# Sensor_Board.net
KiCad netlist of a schematic drawn in Altium Designer
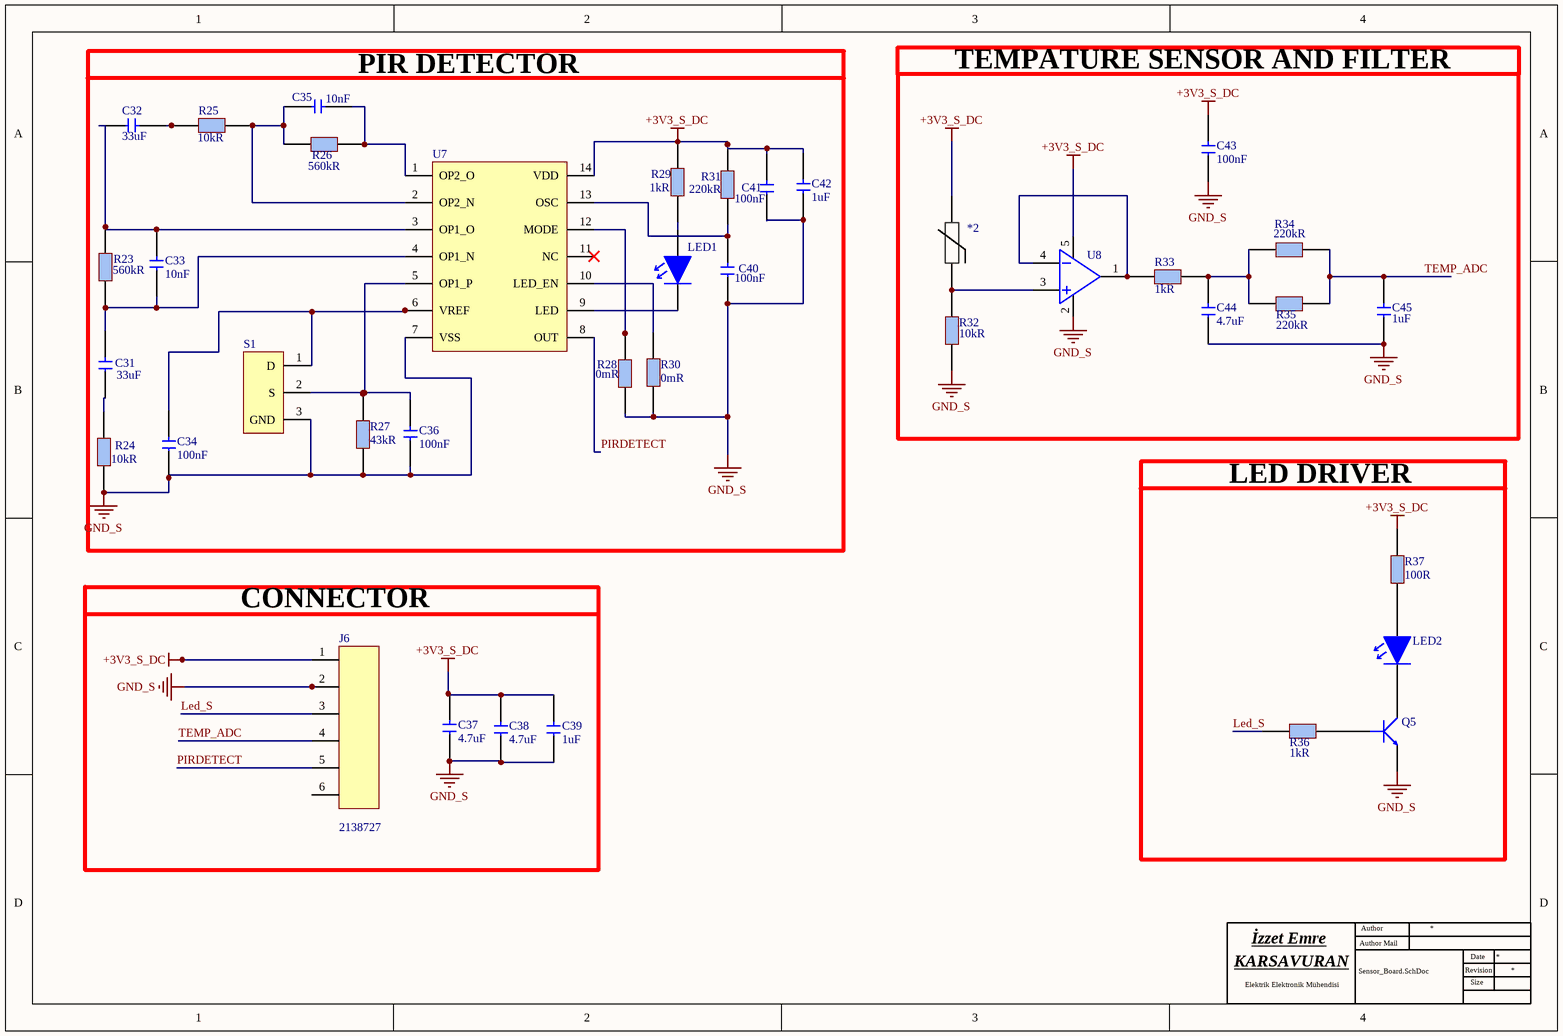
[diagram p0: Sensor_Board.SchDoc]

(export (version "E")
  (design (tool "Eeschema 10.0.6"))
  (components
    (comp (ref "*2")
      (value "TFPT1206L1002FM")
      (footprint "RES_1206")
      (description "Thermistor PTC 10K Ohm 1% 2-Pin 1206 Surface Mount Solder Pad T/R Automotive")
      (fields
        (field (name "MANUFACTURER") "Vishay Dale")
        (field (name "TOLERANCE") "1%")
        (field (name "DESIGNED BY") "İzzet Emre KARSAVURAN")
      )
      (libsource (lib "burglar_alarm_system_Library") (part "TFPT1206L1002FM"))
    )
    (comp (ref "C31")
      (value "C3216X5R1E336M160AC")
      (footprint "CAP_1206")
      (description "Cap Ceramic 33uF 25V X5R 20% SMD 1206 85C T/R")
      (fields
        (field (name "MANUFACTURER") "TDK")
        (field (name "TOLERANCE") "20%")
        (field (name "CAPACITANCE") "33uF")
        (field (name "DESIGNED BY") "İzzet Emre KARSAVURAN")
      )
      (libsource (lib "burglar_alarm_system_Library") (part "CAP CER 33uF"))
    )
    (comp (ref "C32")
      (value "C3216X5R1E336M160AC")
      (footprint "CAP_1206")
      (description "Cap Ceramic 33uF 25V X5R 20% SMD 1206 85C T/R")
      (fields
        (field (name "MANUFACTURER") "TDK")
        (field (name "TOLERANCE") "20%")
        (field (name "CAPACITANCE") "33uF")
        (field (name "DESIGNED BY") "İzzet Emre KARSAVURAN")
      )
      (libsource (lib "burglar_alarm_system_Library") (part "CAP CER 33uF"))
    )
    (comp (ref "C33")
      (value "0603B103K160CT")
      (footprint "CAP_0603")
      (fields
        (field (name "MANUFACTURER") "Walsin Technologies")
        (field (name "TOLERANCE") "10%")
        (field (name "CAPACITANCE") "10nF")
        (field (name "DESIGNED BY") "İzzet Emre KARSAVURAN")
      )
      (libsource (lib "burglar_alarm_system_Library") (part "CAP CER 10nF"))
    )
    (comp (ref "C34")
      (value "CL21B104KBCNNNC")
      (footprint "CAP_0805")
      (fields
        (field (name "MANUFACTURER") "Samsung")
        (field (name "TOLERANCE") "10%")
        (field (name "VOLTAGE") "50V")
        (field (name "CAPACITANCE") "100nF")
        (field (name "DESIGNED BY") "İzzet Emre KARSAVURAN")
      )
      (libsource (lib "burglar_alarm_system_Library") (part "CAP CER 100nF-0803"))
    )
    (comp (ref "C35")
      (value "0603B103K160CT")
      (footprint "CAP_0603")
      (fields
        (field (name "MANUFACTURER") "Walsin Technologies")
        (field (name "TOLERANCE") "10%")
        (field (name "CAPACITANCE") "10nF")
        (field (name "DESIGNED BY") "İzzet Emre KARSAVURAN")
      )
      (libsource (lib "burglar_alarm_system_Library") (part "CAP CER 10nF"))
    )
    (comp (ref "C36")
      (value "CL21B104KBCNNNC")
      (footprint "CAP_0805")
      (fields
        (field (name "MANUFACTURER") "Samsung")
        (field (name "TOLERANCE") "10%")
        (field (name "VOLTAGE") "50V")
        (field (name "CAPACITANCE") "100nF")
        (field (name "DESIGNED BY") "İzzet Emre KARSAVURAN")
      )
      (libsource (lib "burglar_alarm_system_Library") (part "CAP CER 100nF-0803"))
    )
    (comp (ref "C37")
      (value "CL21A475KAQNNNE")
      (footprint "CAP_0805")
      (fields
        (field (name "MANUFACTURER") "Samsung")
        (field (name "TOLERANCE") "10%")
        (field (name "CAPACITANCE") "4.7uF")
        (field (name "DESIGNED BY") "İzzet Emre KARSAVURAN")
      )
      (libsource (lib "burglar_alarm_system_Library") (part "CAP CER 4.7uF"))
    )
    (comp (ref "C38")
      (value "CL21A475KAQNNNE")
      (footprint "CAP_0805")
      (fields
        (field (name "MANUFACTURER") "Samsung")
        (field (name "TOLERANCE") "10%")
        (field (name "CAPACITANCE") "4.7uF")
        (field (name "DESIGNED BY") "İzzet Emre KARSAVURAN")
      )
      (libsource (lib "burglar_alarm_system_Library") (part "CAP CER 4.7uF"))
    )
    (comp (ref "C39")
      (value "CL21B105KBFNNNE")
      (footprint "CAP_0805")
      (fields
        (field (name "MANUFACTURER") "Samsung")
        (field (name "TOLERANCE") "10%")
        (field (name "VOLTAGE") "50V")
        (field (name "CAPACITANCE") "1uF")
        (field (name "DESIGNED BY") "İzzet Emre KARSAVURAN")
      )
      (libsource (lib "burglar_alarm_system_Library") (part "CAP CER 1uF"))
    )
    (comp (ref "C40")
      (value "CL21B104KBCNNNC")
      (footprint "CAP_0805")
      (fields
        (field (name "MANUFACTURER") "Samsung")
        (field (name "TOLERANCE") "10%")
        (field (name "VOLTAGE") "50V")
        (field (name "CAPACITANCE") "100nF")
        (field (name "DESIGNED BY") "İzzet Emre KARSAVURAN")
      )
      (libsource (lib "burglar_alarm_system_Library") (part "CAP CER 100nF-0803"))
    )
    (comp (ref "C41")
      (value "CL21B104KBCNNNC")
      (footprint "CAP_0805")
      (fields
        (field (name "MANUFACTURER") "Samsung")
        (field (name "TOLERANCE") "10%")
        (field (name "VOLTAGE") "50V")
        (field (name "CAPACITANCE") "100nF")
        (field (name "DESIGNED BY") "İzzet Emre KARSAVURAN")
      )
      (libsource (lib "burglar_alarm_system_Library") (part "CAP CER 100nF-0803"))
    )
    (comp (ref "C42")
      (value "CL21B105KBFNNNE")
      (footprint "CAP_0805")
      (fields
        (field (name "MANUFACTURER") "Samsung")
        (field (name "TOLERANCE") "10%")
        (field (name "VOLTAGE") "50V")
        (field (name "CAPACITANCE") "1uF")
        (field (name "DESIGNED BY") "İzzet Emre KARSAVURAN")
      )
      (libsource (lib "burglar_alarm_system_Library") (part "CAP CER 1uF"))
    )
    (comp (ref "C43")
      (value "C0603C104K5RACTU")
      (footprint "CAP_0603")
      (description "Multilayer Ceramic Capacitors (MLCC) - SMD/SMT 50volts 0.1uF X7R 10%")
      (fields
        (field (name "MANUFACTURER") "KEMET")
        (field (name "TOLERANCE") "10%")
        (field (name "CAPACITANCE") "100nF")
        (field (name "DESIGNED BY") "İzzet Emre KARSAVURAN")
      )
      (libsource (lib "burglar_alarm_system_Library") (part "CAP CER 100nF 0603"))
    )
    (comp (ref "C44")
      (value "CL21A475KAQNNNE")
      (footprint "CAP_0805")
      (fields
        (field (name "MANUFACTURER") "Samsung")
        (field (name "TOLERANCE") "10%")
        (field (name "CAPACITANCE") "4.7uF")
        (field (name "DESIGNED BY") "İzzet Emre KARSAVURAN")
      )
      (libsource (lib "burglar_alarm_system_Library") (part "CAP CER 4.7uF"))
    )
    (comp (ref "C45")
      (value "CL21B105KBFNNNE")
      (footprint "CAP_0805")
      (fields
        (field (name "MANUFACTURER") "Samsung")
        (field (name "TOLERANCE") "10%")
        (field (name "VOLTAGE") "50V")
        (field (name "CAPACITANCE") "1uF")
        (field (name "DESIGNED BY") "İzzet Emre KARSAVURAN")
      )
      (libsource (lib "burglar_alarm_system_Library") (part "CAP CER 1uF"))
    )
    (comp (ref "J6")
      (value "64800611622")
      (footprint "64800611622")
      (fields
        (field (name "MANUFACTURER") "Wurth Electronics")
        (field (name "SUPPLIER PART NUMBER 1") "2138727")
        (field (name "DESIGNED BY") "İzzet Emre KARSAVURAN")
      )
      (libsource (lib "burglar_alarm_system_Library") (part "64800611622_conn_6pin"))
    )
    (comp (ref "LED1")
      (value "LTST-C171GKT")
      (footprint "LED_GREEN_0805")
      (description "Green 0805 130 º Min 5 mcd Typical 12 mcd Water Clear Lens SMT LED")
      (fields
        (field (name "MANUFACTURER") "Vishay Lite-On")
        (field (name "DESIGNED BY") "İzzet Emre KARSAVURAN")
      )
      (libsource (lib "burglar_alarm_system_Library") (part "LED GREEN 0805"))
    )
    (comp (ref "LED2")
      (value "LH R974-LP-1")
      (footprint "LED_RED_0805")
      (description "LED Uni-Color Red 660nm T/R")
      (fields (field (name "MANUFACTURER") "Osram Opto") (field (name "DESIGNED BY") "İzzet Emre KARSAVURAN"))
      (libsource (lib "burglar_alarm_system_Library") (part "LED RED 0805"))
    )
    (comp (ref "Q5")
      (value "MMBT3904-7-F")
      (footprint "SOT23-F")
      (description "TRANS NPN 40V 0.2A SMD SOT23-3")
      (fields
        (field (name "MANUFACTURER") "Diodes Zetex")
        (field (name "DESIGNED BY") "İzzet Emre KARSAVURAN")
      )
      (libsource (lib "burglar_alarm_system_Library") (part "MMBT3904-7-F"))
    )
    (comp (ref "R23")
      (value "RC0603JR-07560KL")
      (footprint "RES_0603")
      (description "RES SMD 560K OHM 5% 1/10W 0603")
      (fields
        (field (name "MANUFACTURER") "Yageo")
        (field (name "TOLERANCE") "5%")
        (field (name "RESISTANCE") "560kR")
        (field (name "DESIGNED BY") "İzzet Emre KARSAVURAN")
      )
      (libsource (lib "") (part "RES 560k OHM_1"))
    )
    (comp (ref "R24")
      (value "RC0603FR-0710KL")
      (footprint "RES_0603")
      (description "Res General Purpose Thick Film 0603 10K Ohm 1% 1/10W ±100ppm/°C Molded SMD Paper T/R")
      (fields
        (field (name "MANUFACTURER") "Yageo")
        (field (name "TOLERANCE") "1%")
        (field (name "RESISTANCE") "10kR")
        (field (name "DESIGNED BY") "İzzet Emre Karsavuran")
      )
      (libsource (lib "") (part "RES 10K OHM 0603_1"))
    )
    (comp (ref "R25")
      (value "RC0603FR-0710KL")
      (footprint "RES_0603")
      (description "Res General Purpose Thick Film 0603 10K Ohm 1% 1/10W ±100ppm/°C Molded SMD Paper T/R")
      (fields
        (field (name "MANUFACTURER") "Yageo")
        (field (name "TOLERANCE") "1%")
        (field (name "RESISTANCE") "10kR")
        (field (name "DESIGNED BY") "İzzet Emre Karsavuran")
      )
      (libsource (lib "burglar_alarm_system_Library") (part "RES 10K OHM 0603"))
    )
    (comp (ref "R26")
      (value "RC0603JR-07560KL")
      (footprint "RES_0603")
      (description "RES SMD 560K OHM 5% 1/10W 0603")
      (fields
        (field (name "MANUFACTURER") "Yageo")
        (field (name "TOLERANCE") "5%")
        (field (name "RESISTANCE") "560kR")
        (field (name "DESIGNED BY") "İzzet Emre KARSAVURAN")
      )
      (libsource (lib "burglar_alarm_system_Library") (part "RES 560k OHM"))
    )
    (comp (ref "R27")
      (value "RC0603JR-0743KL")
      (footprint "RES_0603")
      (fields
        (field (name "MANUFACTURER") "Yageo")
        (field (name "TOLERANCE") "5%")
        (field (name "RESISTANCE") "43kR")
        (field (name "DESIGNED BY") "İzzet Emre KARSAVURAN")
      )
      (libsource (lib "burglar_alarm_system_Library") (part "RES 43K OHM"))
    )
    (comp (ref "R28")
      (value "RC0603JR-070RL")
      (footprint "RES_0603")
      (description "RES SMD 0 OHM JUMPER 1/10W 0603")
      (fields
        (field (name "MANUFACTURER") "Yageo")
        (field (name "TOLERANCE") "1%")
        (field (name "RESISTANCE") "0mR")
        (field (name "DESIGNED BY") "İzzet Emre Karsavuran")
      )
      (libsource (lib "burglar_alarm_system_Library") (part "RES 0 OHM"))
    )
    (comp (ref "R29")
      (value "RC0603FR-0710KL")
      (footprint "RES_0603")
      (fields
        (field (name "MANUFACTURER") "Yageo")
        (field (name "TOLERANCE") "1%")
        (field (name "RESISTANCE") "1kR")
        (field (name "DESIGNED BY") "İzzet Emre KARSAVURAN")
      )
      (libsource (lib "burglar_alarm_system_Library") (part "RES 1k OHM"))
    )
    (comp (ref "R30")
      (value "RC0603JR-070RL")
      (footprint "RES_0603")
      (description "RES SMD 0 OHM JUMPER 1/10W 0603")
      (fields
        (field (name "MANUFACTURER") "Yageo")
        (field (name "TOLERANCE") "1%")
        (field (name "RESISTANCE") "0mR")
        (field (name "DESIGNED BY") "İzzet Emre Karsavuran")
      )
      (libsource (lib "burglar_alarm_system_Library") (part "RES 0 OHM"))
    )
    (comp (ref "R31")
      (value "RC0603JR-07220KL")
      (footprint "RES_0603")
      (fields
        (field (name "MANUFACTURER") "Yageo")
        (field (name "TOLERANCE") "5%")
        (field (name "RESISTANCE") "220kR")
        (field (name "DESIGNED BY") "İzzet Emre KARSAVURAN")
      )
      (libsource (lib "") (part "RES 220k OHM_1"))
    )
    (comp (ref "R32")
      (value "RC0603FR-0710KL")
      (footprint "RES_0603")
      (description "Res General Purpose Thick Film 0603 10K Ohm 1% 1/10W ±100ppm/°C Molded SMD Paper T/R")
      (fields
        (field (name "MANUFACTURER") "Yageo")
        (field (name "TOLERANCE") "1%")
        (field (name "RESISTANCE") "10kR")
        (field (name "DESIGNED BY") "İzzet Emre Karsavuran")
      )
      (libsource (lib "") (part "RES 10K OHM 0603_1"))
    )
    (comp (ref "R33")
      (value "RC0603FR-0710KL")
      (footprint "RES_0603")
      (description "Res General Purpose Thick Film 0603 10K Ohm 1% 1/10W ±100ppm/°C Molded SMD Paper T/R")
      (fields
        (field (name "MANUFACTURER") "Yageo")
        (field (name "TOLERANCE") "1%")
        (field (name "RESISTANCE") "1kR")
        (field (name "DESIGNED BY") "İzzet Emre KARSAVURAN")
      )
      (libsource (lib "") (part "RES 1k OHM_1"))
    )
    (comp (ref "R34")
      (value "RC0603JR-07220KL")
      (footprint "RES_0603")
      (fields
        (field (name "MANUFACTURER") "Yageo")
        (field (name "TOLERANCE") "5%")
        (field (name "RESISTANCE") "220kR")
        (field (name "DESIGNED BY") "İzzet Emre KARSAVURAN")
      )
      (libsource (lib "burglar_alarm_system_Library") (part "RES 220k OHM"))
    )
    (comp (ref "R35")
      (value "RC0603JR-07220KL")
      (footprint "RES_0603")
      (fields
        (field (name "MANUFACTURER") "Yageo")
        (field (name "TOLERANCE") "5%")
        (field (name "RESISTANCE") "220kR")
        (field (name "DESIGNED BY") "İzzet Emre KARSAVURAN")
      )
      (libsource (lib "burglar_alarm_system_Library") (part "RES 220k OHM"))
    )
    (comp (ref "R36")
      (value "RC0603FR-0710KL")
      (footprint "RES_0603")
      (description "Res General Purpose Thick Film 0603 10K Ohm 1% 1/10W ±100ppm/°C Molded SMD Paper T/R")
      (fields
        (field (name "MANUFACTURER") "Yageo")
        (field (name "TOLERANCE") "1%")
        (field (name "RESISTANCE") "1kR")
        (field (name "DESIGNED BY") "İzzet Emre KARSAVURAN")
      )
      (libsource (lib "") (part "RES 1k OHM_1"))
    )
    (comp (ref "R37")
      (value "RC0603JR-07100RL")
      (footprint "RES_0603")
      (description "Res Thick Film 0603 100 Ohm 5% 0.1W(1/10W) ±100ppm/C Molded SMD Paper T/R")
      (fields
        (field (name "MANUFACTURER") "Yageo")
        (field (name "TOLERANCE") "5%")
        (field (name "RESISTANCE") "100R")
        (field (name "DESIGNED BY") "İzzet Emre KARSAVURAN")
      )
      (libsource (lib "burglar_alarm_system_Library") (part "RES 100 OHM"))
    )
    (comp (ref "S1")
      (value "LHI 878/3902")
      (footprint "LHI 878")
      (description "Sensor PIR (Passive Infrared) - - TO-205AA, TO-5-3 Metal Can")
      (fields (field (name "DESIGNED BY") "İzzet Emre KARSAVURAN"))
      (libsource (lib "burglar_alarm_system_Library") (part "LHI 878/3902"))
    )
    (comp (ref "U7")
      (value "NCS36000DRG")
      (footprint "SOIC14")
      (description "Low Noise Amplifiers and LDO Regulator 14-Pin SOIC N T/R")
      (fields
        (field (name "MANUFACTURER") "ON Semiconductor")
        (field (name "DESIGNED BY") "İzzet Emre KARSAVURAN")
      )
      (libsource (lib "burglar_alarm_system_Library") (part "NCS36000"))
    )
    (comp (ref "U8")
      (value "OPA314AIDBVR")
      (footprint "SOT23-5")
      (description "Op Amp")
      (fields
        (field (name "MANUFACTURER") "Texas Instruments")
        (field (name "DESIGNED BY") "İzzet Emre KARSAVURAN")
      )
      (libsource (lib "burglar_alarm_system_Library") (part "OPA314"))
    )
  )
  (nets
    (net (code "1") (name "+3V3_S_DC") (class "Default")
      (node (ref "*2") (pin "2") (pinfunction "2_2") (pintype "passive"))
      (node (ref "C37") (pin "2") (pinfunction "2_2") (pintype "passive"))
      (node (ref "C38") (pin "2") (pinfunction "2_2") (pintype "passive"))
      (node (ref "C39") (pin "2") (pinfunction "2_2") (pintype "passive"))
      (node (ref "C41") (pin "2") (pinfunction "2_2") (pintype "passive"))
      (node (ref "C42") (pin "2") (pinfunction "2_2") (pintype "passive"))
      (node (ref "C43") (pin "2") (pinfunction "2_2") (pintype "passive"))
      (node (ref "J6") (pin "1") (pintype "power_in"))
      (node (ref "R29") (pin "2") (pinfunction "2_2") (pintype "passive"))
      (node (ref "R31") (pin "2") (pinfunction "2_2") (pintype "passive"))
      (node (ref "R37") (pin "1") (pinfunction "1_1") (pintype "passive"))
      (node (ref "U7") (pin "14") (pinfunction "VDD_14") (pintype "passive"))
      (node (ref "U8") (pin "5") (pinfunction "5_5") (pintype "passive"))
    )
    (net (code "2") (name "/Led_S") (class "Default")
      (node (ref "J6") (pin "3") (pintype "power_in"))
      (node (ref "R36") (pin "1") (pinfunction "1_1") (pintype "passive"))
    )
    (net (code "3") (name "/PIRDETECT") (class "Default")
      (node (ref "J6") (pin "5") (pintype "power_in"))
      (node (ref "U7") (pin "8") (pinfunction "OUT_8") (pintype "passive"))
    )
    (net (code "4") (name "/TEMP_ADC") (class "Default")
      (node (ref "C45") (pin "2") (pinfunction "2_2") (pintype "passive"))
      (node (ref "J6") (pin "4") (pintype "power_in"))
      (node (ref "R34") (pin "2") (pinfunction "2_2") (pintype "passive"))
      (node (ref "R35") (pin "2") (pinfunction "2_2") (pintype "passive"))
    )
    (net (code "5") (name "GND_S") (class "Default")
      (node (ref "C34") (pin "1") (pinfunction "1_1") (pintype "passive"))
      (node (ref "C36") (pin "1") (pinfunction "1_1") (pintype "passive"))
      (node (ref "C37") (pin "1") (pinfunction "1_1") (pintype "passive"))
      (node (ref "C38") (pin "1") (pinfunction "1_1") (pintype "passive"))
      (node (ref "C39") (pin "1") (pinfunction "1_1") (pintype "passive"))
      (node (ref "C40") (pin "1") (pinfunction "1_1") (pintype "passive"))
      (node (ref "C41") (pin "1") (pinfunction "1_1") (pintype "passive"))
      (node (ref "C42") (pin "1") (pinfunction "1_1") (pintype "passive"))
      (node (ref "C43") (pin "1") (pinfunction "1_1") (pintype "passive"))
      (node (ref "C44") (pin "1") (pinfunction "1_1") (pintype "passive"))
      (node (ref "C45") (pin "1") (pinfunction "1_1") (pintype "passive"))
      (node (ref "J6") (pin "2") (pintype "power_in"))
      (node (ref "Q5") (pin "2") (pinfunction "E_2") (pintype "power_in"))
      (node (ref "R24") (pin "1") (pinfunction "1_1") (pintype "passive"))
      (node (ref "R27") (pin "1") (pinfunction "1_1") (pintype "passive"))
      (node (ref "R28") (pin "1") (pinfunction "1_1") (pintype "passive"))
      (node (ref "R30") (pin "1") (pinfunction "1_1") (pintype "passive"))
      (node (ref "R32") (pin "1") (pinfunction "1_1") (pintype "passive"))
      (node (ref "S1") (pin "3") (pinfunction "GND_3") (pintype "passive"))
      (node (ref "U7") (pin "7") (pinfunction "VSS_7") (pintype "passive"))
      (node (ref "U8") (pin "2") (pinfunction "2_2") (pintype "passive"))
    )
    (net (code "6") (name "Net-(*2-Pad1)") (class "Default")
      (node (ref "*2") (pin "1") (pinfunction "1_1") (pintype "passive"))
      (node (ref "R32") (pin "2") (pinfunction "2_2") (pintype "passive"))
      (node (ref "U8") (pin "3") (pinfunction "3_3") (pintype "passive"))
    )
    (net (code "7") (name "Net-(C31-Pad1)") (class "Default")
      (node (ref "C31") (pin "1") (pinfunction "1_1") (pintype "passive"))
      (node (ref "R24") (pin "2") (pinfunction "2_2") (pintype "passive"))
    )
    (net (code "8") (name "Net-(C32-Pad2)") (class "Default")
      (node (ref "C32") (pin "2") (pinfunction "2_2") (pintype "passive"))
      (node (ref "R25") (pin "1") (pinfunction "1_1") (pintype "passive"))
    )
    (net (code "9") (name "Net-(C44-Pad2)") (class "Default")
      (node (ref "C44") (pin "2") (pinfunction "2_2") (pintype "passive"))
      (node (ref "R33") (pin "2") (pinfunction "2_2") (pintype "passive"))
      (node (ref "R34") (pin "1") (pinfunction "1_1") (pintype "passive"))
      (node (ref "R35") (pin "1") (pinfunction "1_1") (pintype "passive"))
    )
    (net (code "10") (name "Net-(LED1-Pad2)") (class "Default")
      (node (ref "LED1") (pin "2") (pinfunction "2_2") (pintype "power_in"))
      (node (ref "R29") (pin "1") (pinfunction "1_1") (pintype "passive"))
    )
    (net (code "11") (name "Net-(LED2-Pad2)") (class "Default")
      (node (ref "LED2") (pin "2") (pinfunction "2_2") (pintype "power_in"))
      (node (ref "R37") (pin "2") (pinfunction "2_2") (pintype "passive"))
    )
    (net (code "12") (name "Net-(Q5-B)") (class "Default")
      (node (ref "Q5") (pin "1") (pinfunction "B_1") (pintype "power_in"))
      (node (ref "R36") (pin "2") (pinfunction "2_2") (pintype "passive"))
    )
    (net (code "13") (name "Net-(Q5-C)") (class "Default")
      (node (ref "LED2") (pin "1") (pinfunction "1_1") (pintype "power_in"))
      (node (ref "Q5") (pin "3") (pinfunction "C_3") (pintype "power_in"))
    )
    (net (code "14") (name "Net-(R33-Pad1)") (class "Default")
      (node (ref "R33") (pin "1") (pinfunction "1_1") (pintype "passive"))
      (node (ref "U8") (pin "1") (pinfunction "1_1") (pintype "passive"))
      (node (ref "U8") (pin "4") (pinfunction "4_4") (pintype "passive"))
    )
    (net (code "15") (name "Net-(S1-D)") (class "Default")
      (node (ref "C34") (pin "2") (pinfunction "2_2") (pintype "passive"))
      (node (ref "S1") (pin "1") (pinfunction "D_1") (pintype "passive"))
      (node (ref "U7") (pin "6") (pinfunction "VREF_6") (pintype "passive"))
    )
    (net (code "16") (name "Net-(S1-S)") (class "Default")
      (node (ref "C36") (pin "2") (pinfunction "2_2") (pintype "passive"))
      (node (ref "R27") (pin "2") (pinfunction "2_2") (pintype "passive"))
      (node (ref "S1") (pin "2") (pinfunction "S_2") (pintype "passive"))
      (node (ref "U7") (pin "5") (pinfunction "OP1_P_5") (pintype "passive"))
    )
    (net (code "17") (name "Net-(U7-LED)") (class "Default")
      (node (ref "LED1") (pin "1") (pinfunction "1_1") (pintype "power_in"))
      (node (ref "U7") (pin "9") (pinfunction "LED_9") (pintype "passive"))
    )
    (net (code "18") (name "Net-(U7-LED_EN)") (class "Default")
      (node (ref "R30") (pin "2") (pinfunction "2_2") (pintype "passive"))
      (node (ref "U7") (pin "10") (pinfunction "LED_EN_10") (pintype "passive"))
    )
    (net (code "19") (name "Net-(U7-MODE)") (class "Default")
      (node (ref "R28") (pin "2") (pinfunction "2_2") (pintype "passive"))
      (node (ref "U7") (pin "12") (pinfunction "MODE_12") (pintype "passive"))
    )
    (net (code "20") (name "Net-(U7-OP1_N)") (class "Default")
      (node (ref "C31") (pin "2") (pinfunction "2_2") (pintype "passive"))
      (node (ref "C33") (pin "1") (pinfunction "1_1") (pintype "passive"))
      (node (ref "R23") (pin "1") (pinfunction "1_1") (pintype "passive"))
      (node (ref "U7") (pin "4") (pinfunction "OP1_N_4") (pintype "passive"))
    )
    (net (code "21") (name "Net-(U7-OP1_O)") (class "Default")
      (node (ref "C32") (pin "1") (pinfunction "1_1") (pintype "passive"))
      (node (ref "C33") (pin "2") (pinfunction "2_2") (pintype "passive"))
      (node (ref "R23") (pin "2") (pinfunction "2_2") (pintype "passive"))
      (node (ref "U7") (pin "3") (pinfunction "OP1_O_3") (pintype "passive"))
    )
    (net (code "22") (name "Net-(U7-OP2_N)") (class "Default")
      (node (ref "C35") (pin "1") (pinfunction "1_1") (pintype "passive"))
      (node (ref "R25") (pin "2") (pinfunction "2_2") (pintype "passive"))
      (node (ref "R26") (pin "1") (pinfunction "1_1") (pintype "passive"))
      (node (ref "U7") (pin "2") (pinfunction "OP2_N_2") (pintype "passive"))
    )
    (net (code "23") (name "Net-(U7-OP2_O)") (class "Default")
      (node (ref "C35") (pin "2") (pinfunction "2_2") (pintype "passive"))
      (node (ref "R26") (pin "2") (pinfunction "2_2") (pintype "passive"))
      (node (ref "U7") (pin "1") (pinfunction "OP2_O_1") (pintype "passive"))
    )
    (net (code "24") (name "Net-(U7-OSC)") (class "Default")
      (node (ref "C40") (pin "2") (pinfunction "2_2") (pintype "passive"))
      (node (ref "R31") (pin "1") (pinfunction "1_1") (pintype "passive"))
      (node (ref "U7") (pin "13") (pinfunction "OSC_13") (pintype "passive"))
    )
    (net (code "25") (name "unconnected-(J6-Pad6)") (class "Default")
      (node (ref "J6") (pin "6") (pintype "power_in"))
    )
    (net (code "26") (name "unconnected-(U7-NC-Pad11)") (class "Default")
      (node (ref "U7") (pin "11") (pinfunction "NC_11") (pintype "passive+no_connect"))
    )
  )
)
